# power_supply_bot.net
KiCad netlist of a schematic drawn in EAGLE
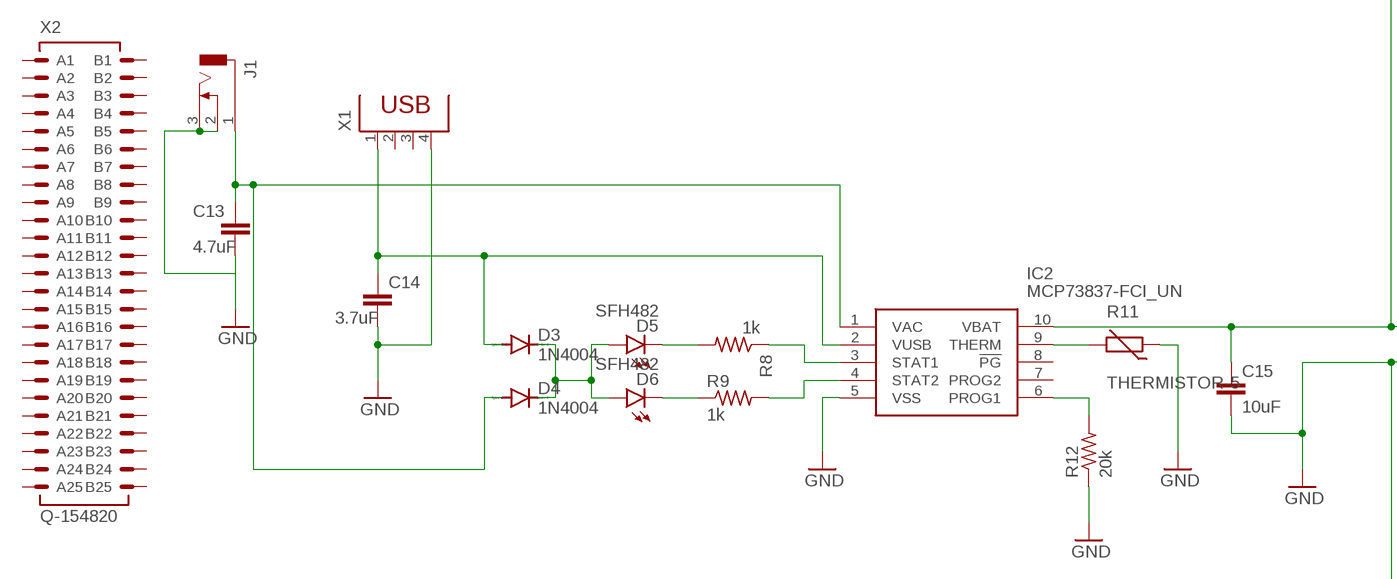
[diagram p0: schematic, sheet 1, part 1 of 2]
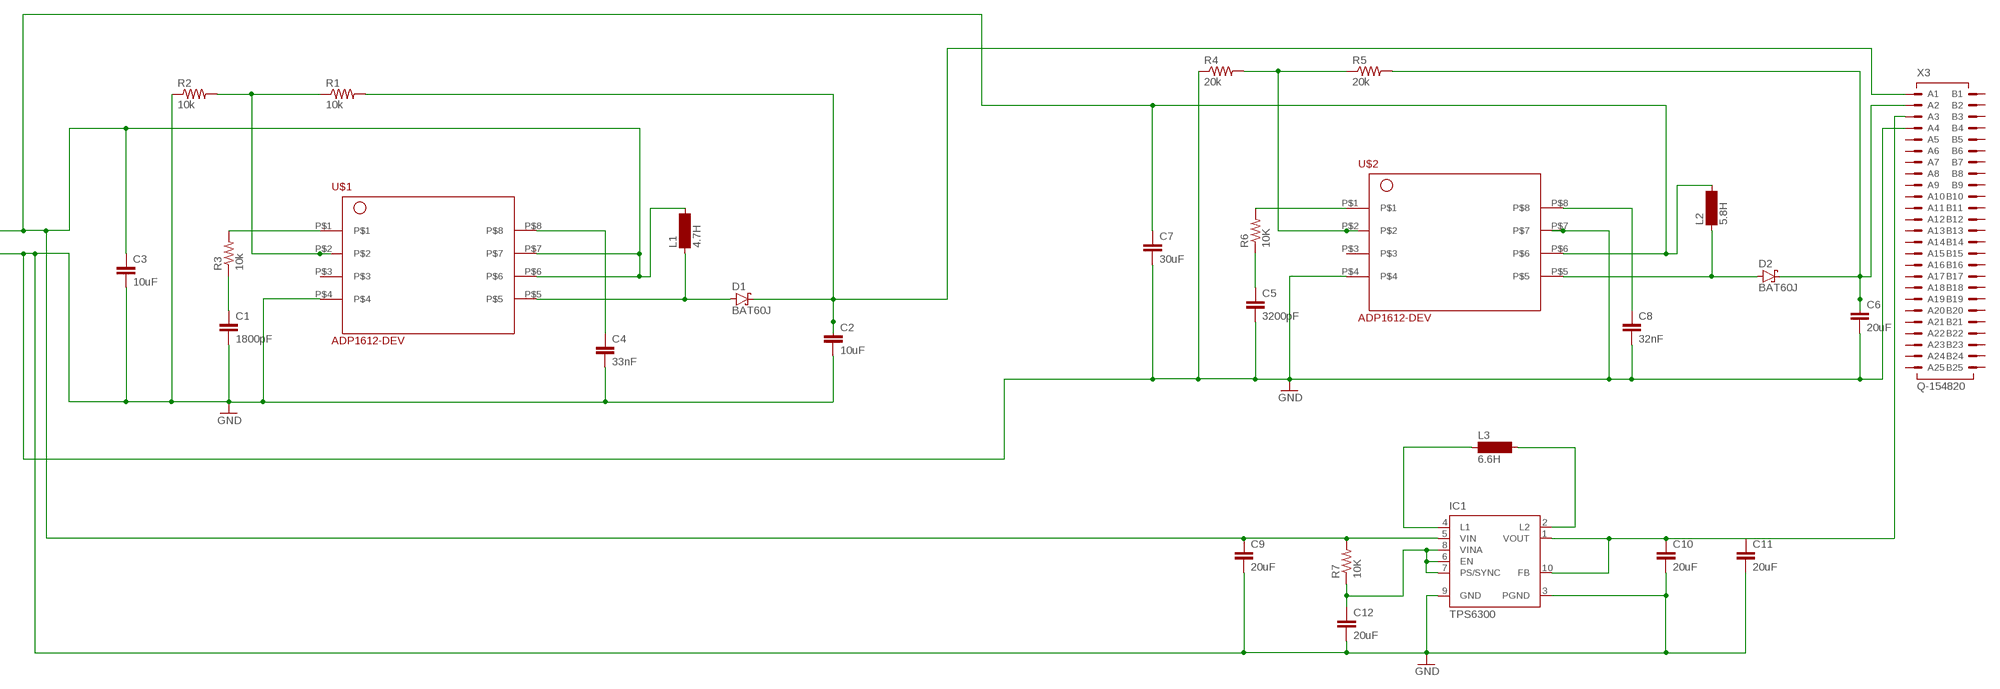
[diagram p1: schematic, sheet 1, part 2 of 2]

(export (version "E")
  (design (tool "Eeschema 10.0.6"))
  (components
    (comp (ref "C1")
      (value "1800pF")
      (footprint "eagle-import:C2.5-4")
      (libsource (lib "eagle-import") (part "C2.5/4"))
    )
    (comp (ref "C2")
      (value "10uF")
      (footprint "eagle-import:C2.5-4")
      (libsource (lib "eagle-import") (part "C2.5/4"))
    )
    (comp (ref "C3")
      (value "10uF")
      (footprint "eagle-import:C2.5-4")
      (libsource (lib "eagle-import") (part "C2.5/4"))
    )
    (comp (ref "C4")
      (value "33nF")
      (footprint "eagle-import:C2.5-4")
      (libsource (lib "eagle-import") (part "C2.5/4"))
    )
    (comp (ref "C5")
      (value "3200pF")
      (footprint "eagle-import:C2.5-4")
      (libsource (lib "eagle-import") (part "C2.5/4"))
    )
    (comp (ref "C6")
      (value "20uF")
      (footprint "eagle-import:C2.5-4")
      (libsource (lib "eagle-import") (part "C2.5/4"))
    )
    (comp (ref "C7")
      (value "30uF")
      (footprint "eagle-import:C2.5-4")
      (libsource (lib "eagle-import") (part "C2.5/4"))
    )
    (comp (ref "C8")
      (value "32nF")
      (footprint "eagle-import:C2.5-4")
      (libsource (lib "eagle-import") (part "C2.5/4"))
    )
    (comp (ref "C9")
      (value "20uF")
      (footprint "eagle-import:C2.5-3")
      (libsource (lib "eagle-import") (part "C2,5-3"))
    )
    (comp (ref "C10")
      (value "20uF")
      (footprint "eagle-import:C2.5-3")
      (libsource (lib "eagle-import") (part "C2,5-3"))
    )
    (comp (ref "C11")
      (value "20uF")
      (footprint "eagle-import:C2.5-3")
      (libsource (lib "eagle-import") (part "C2,5-3"))
    )
    (comp (ref "C12")
      (value "20uF")
      (footprint "eagle-import:C2.5-3")
      (libsource (lib "eagle-import") (part "C2,5-3"))
    )
    (comp (ref "C13")
      (value "4.7uF")
      (footprint "eagle-import:C2.5-3")
      (libsource (lib "eagle-import") (part "C2,5-3"))
    )
    (comp (ref "C14")
      (value "3.7uF")
      (footprint "eagle-import:C2.5-3")
      (libsource (lib "eagle-import") (part "C2,5-3"))
    )
    (comp (ref "C15")
      (value "10uF")
      (footprint "eagle-import:C2.5-3")
      (libsource (lib "eagle-import") (part "C2,5-3"))
    )
    (comp (ref "D1")
      (value "BAT60J")
      (footprint "eagle-import:SOD323_ST")
      (libsource (lib "eagle-import") (part "BAT60J"))
    )
    (comp (ref "D2")
      (value "BAT60J")
      (footprint "eagle-import:SOD323_ST")
      (libsource (lib "eagle-import") (part "BAT60J"))
    )
    (comp (ref "D3")
      (value "1N4004")
      (footprint "eagle-import:DO41-10")
      (libsource (lib "eagle-import") (part "1N4004"))
    )
    (comp (ref "D4")
      (value "1N4004")
      (footprint "eagle-import:DO41-10")
      (libsource (lib "eagle-import") (part "1N4004"))
    )
    (comp (ref "D5")
      (value "SFH482")
      (footprint "eagle-import:SFH482")
      (libsource (lib "eagle-import") (part "SFH482"))
    )
    (comp (ref "D6")
      (value "SFH482")
      (footprint "eagle-import:SFH482")
      (libsource (lib "eagle-import") (part "SFH482"))
    )
    (comp (ref "IC1")
      (value "TPS6300")
      (footprint "eagle-import:DRC-S-PVSON-N10")
      (fields (field (name "MPN") "TPS63000DRCTG4"))
      (libsource (lib "eagle-import") (part "TPS6300"))
    )
    (comp (ref "IC2")
      (value "MCP73837-FCI_UN")
      (footprint "eagle-import:SOP50P490X110-10N")
      (fields
        (field (name "ARROW_PART_NUMBER") "MCP73837-FCI/UN")
        (field (name "MOUSER_PART_NUMBER") "579-MCP73837-FCI/UN")
      )
      (libsource (lib "eagle-import") (part "MCP73837-FCI_UN"))
    )
    (comp (ref "J1")
      (value "DCJ0303")
      (footprint "eagle-import:DCJ0303")
      (libsource (lib "eagle-import") (part "DCJ0303"))
    )
    (comp (ref "L1")
      (value "4.7H")
      (footprint "eagle-import:BS11")
      (libsource (lib "eagle-import") (part "BS11"))
    )
    (comp (ref "L2")
      (value "5.8H")
      (footprint "eagle-import:BS11")
      (libsource (lib "eagle-import") (part "BS11"))
    )
    (comp (ref "L3")
      (value "6.6H")
      (footprint "eagle-import:BS75")
      (libsource (lib "eagle-import") (part "BS75"))
    )
    (comp (ref "R1")
      (value "10k")
      (footprint "eagle-import:0204_7")
      (libsource (lib "eagle-import") (part "R-US_0204/7"))
    )
    (comp (ref "R2")
      (value "10k")
      (footprint "eagle-import:0204_7")
      (libsource (lib "eagle-import") (part "R-US_0204/7"))
    )
    (comp (ref "R3")
      (value "10k")
      (footprint "eagle-import:0204_7")
      (libsource (lib "eagle-import") (part "R-US_0204/7"))
    )
    (comp (ref "R4")
      (value "20k")
      (footprint "eagle-import:0204_7")
      (libsource (lib "eagle-import") (part "R-US_0204/7"))
    )
    (comp (ref "R5")
      (value "20k")
      (footprint "eagle-import:0204_7")
      (libsource (lib "eagle-import") (part "R-US_0204/7"))
    )
    (comp (ref "R6")
      (value "10K")
      (footprint "eagle-import:0204_7")
      (libsource (lib "eagle-import") (part "R-US_0204/7"))
    )
    (comp (ref "R7")
      (value "10K")
      (footprint "eagle-import:0204_5")
      (libsource (lib "eagle-import") (part "R-US_0204/5"))
    )
    (comp (ref "R8")
      (value "1k")
      (footprint "eagle-import:0204_5")
      (libsource (lib "eagle-import") (part "R-US_0204/5"))
    )
    (comp (ref "R9")
      (value "1k")
      (footprint "eagle-import:0204_5")
      (libsource (lib "eagle-import") (part "R-US_0204/5"))
    )
    (comp (ref "R11")
      (value "THERMISTOR-5")
      (footprint "eagle-import:R-5")
      (libsource (lib "eagle-import") (part "THERMISTOR-5"))
    )
    (comp (ref "R12")
      (value "20k")
      (footprint "eagle-import:0204_5")
      (libsource (lib "eagle-import") (part "R-US_0204/5"))
    )
    (comp (ref "U$1")
      (value "ADP1612-DEV")
      (footprint "eagle-import:TQFP-ADP1612")
      (libsource (lib "eagle-import") (part "ADP1612-DEV"))
    )
    (comp (ref "U$2")
      (value "ADP1612-DEV")
      (footprint "eagle-import:TQFP-ADP1612")
      (libsource (lib "eagle-import") (part "ADP1612-DEV"))
    )
    (comp (ref "X1")
      (value "PN61729")
      (footprint "eagle-import:PN61729")
      (libsource (lib "eagle-import") (part "PN61729"))
    )
    (comp (ref "X2")
      (value "Q-154820")
      (footprint "eagle-import:154820")
      (libsource (lib "eagle-import") (part "Q-154820"))
    )
    (comp (ref "X3")
      (value "Q-154820")
      (footprint "eagle-import:154820")
      (libsource (lib "eagle-import") (part "Q-154820"))
    )
  )
  (nets
    (net (code "1") (name "GND") (class "Default")
      (node (ref "C1") (pin "2") (pinfunction "2_2") (pintype "passive"))
      (node (ref "C10") (pin "2") (pinfunction "2_2") (pintype "passive"))
      (node (ref "C11") (pin "2") (pinfunction "2_2") (pintype "passive"))
      (node (ref "C12") (pin "2") (pinfunction "2_2") (pintype "passive"))
      (node (ref "C13") (pin "2") (pinfunction "2_2") (pintype "passive"))
      (node (ref "C14") (pin "1") (pinfunction "1_1") (pintype "passive"))
      (node (ref "C14") (pin "2") (pinfunction "2_2") (pintype "passive"))
      (node (ref "C15") (pin "2") (pinfunction "2_2") (pintype "passive"))
      (node (ref "C2") (pin "2") (pinfunction "2_2") (pintype "passive"))
      (node (ref "C3") (pin "2") (pinfunction "2_2") (pintype "passive"))
      (node (ref "C4") (pin "2") (pinfunction "2_2") (pintype "passive"))
      (node (ref "C5") (pin "2") (pinfunction "2_2") (pintype "passive"))
      (node (ref "C6") (pin "2") (pinfunction "2_2") (pintype "passive"))
      (node (ref "C7") (pin "2") (pinfunction "2_2") (pintype "passive"))
      (node (ref "C8") (pin "2") (pinfunction "2_2") (pintype "passive"))
      (node (ref "C9") (pin "2") (pinfunction "2_2") (pintype "passive"))
      (node (ref "D3") (pin "A") (pinfunction "A_A") (pintype "passive"))
      (node (ref "IC1") (pin "3") (pinfunction "PGND_3") (pintype "power_in"))
      (node (ref "IC1") (pin "9") (pinfunction "GND_9") (pintype "power_in"))
      (node (ref "IC2") (pin "2") (pinfunction "VUSB_2") (pintype "bidirectional"))
      (node (ref "IC2") (pin "5") (pinfunction "VSS_5") (pintype "power_in"))
      (node (ref "J1") (pin "2") (pinfunction "2_2") (pintype "passive"))
      (node (ref "J1") (pin "3") (pinfunction "3_3") (pintype "passive"))
      (node (ref "R11") (pin "1") (pinfunction "1_1") (pintype "passive"))
      (node (ref "R12") (pin "1") (pinfunction "1_1") (pintype "passive"))
      (node (ref "R2") (pin "1") (pinfunction "1_1") (pintype "passive"))
      (node (ref "R4") (pin "1") (pinfunction "1_1") (pintype "passive"))
      (node (ref "U$1") (pin "P$4") (pinfunction "P$4_P$4") (pintype "bidirectional"))
      (node (ref "U$2") (pin "P$4") (pinfunction "P$4_P$4") (pintype "bidirectional"))
      (node (ref "U$2") (pin "P$7") (pinfunction "P$7_P$7") (pintype "bidirectional"))
      (node (ref "X1") (pin "1") (pinfunction "1_1") (pintype "passive"))
      (node (ref "X1") (pin "4") (pinfunction "4_4") (pintype "passive"))
      (node (ref "X3") (pin "A4") (pinfunction "A4_A4") (pintype "passive"))
    )
    (net (code "2") (name "Net-(C1-Pad1)") (class "Default")
      (node (ref "C1") (pin "1") (pinfunction "1_1") (pintype "passive"))
      (node (ref "R3") (pin "1") (pinfunction "1_1") (pintype "passive"))
    )
    (net (code "3") (name "Net-(C2-Pad1)") (class "Default")
      (node (ref "C2") (pin "1") (pinfunction "1_1") (pintype "passive"))
      (node (ref "D1") (pin "C") (pinfunction "C_C") (pintype "passive"))
      (node (ref "R1") (pin "2") (pinfunction "2_2") (pintype "passive"))
      (node (ref "X3") (pin "A1") (pinfunction "A1_A1") (pintype "passive"))
    )
    (net (code "4") (name "Net-(C4-Pad1)") (class "Default")
      (node (ref "C4") (pin "1") (pinfunction "1_1") (pintype "passive"))
      (node (ref "U$1") (pin "P$8") (pinfunction "P$8_P$8") (pintype "bidirectional"))
    )
    (net (code "5") (name "Net-(C5-Pad1)") (class "Default")
      (node (ref "C5") (pin "1") (pinfunction "1_1") (pintype "passive"))
      (node (ref "R6") (pin "1") (pinfunction "1_1") (pintype "passive"))
    )
    (net (code "6") (name "Net-(C6-Pad1)") (class "Default")
      (node (ref "C6") (pin "1") (pinfunction "1_1") (pintype "passive"))
      (node (ref "D2") (pin "C") (pinfunction "C_C") (pintype "passive"))
      (node (ref "R5") (pin "2") (pinfunction "2_2") (pintype "passive"))
      (node (ref "X3") (pin "A2") (pinfunction "A2_A2") (pintype "passive"))
    )
    (net (code "7") (name "Net-(C8-Pad1)") (class "Default")
      (node (ref "C8") (pin "1") (pinfunction "1_1") (pintype "passive"))
      (node (ref "U$2") (pin "P$8") (pinfunction "P$8_P$8") (pintype "bidirectional"))
    )
    (net (code "8") (name "Net-(D1-PadA)") (class "Default")
      (node (ref "D1") (pin "A") (pinfunction "A_A") (pintype "passive"))
      (node (ref "L1") (pin "1") (pinfunction "1_1") (pintype "passive"))
      (node (ref "U$1") (pin "P$5") (pinfunction "P$5_P$5") (pintype "bidirectional"))
    )
    (net (code "9") (name "Net-(D2-PadA)") (class "Default")
      (node (ref "D2") (pin "A") (pinfunction "A_A") (pintype "passive"))
      (node (ref "L2") (pin "1") (pinfunction "1_1") (pintype "passive"))
      (node (ref "U$2") (pin "P$5") (pinfunction "P$5_P$5") (pintype "bidirectional"))
    )
    (net (code "10") (name "Net-(D3-PadC)") (class "Default")
      (node (ref "D3") (pin "C") (pinfunction "C_C") (pintype "passive"))
      (node (ref "D4") (pin "C") (pinfunction "C_C") (pintype "passive"))
      (node (ref "D5") (pin "A") (pinfunction "A_A") (pintype "passive"))
      (node (ref "D6") (pin "A") (pinfunction "A_A") (pintype "passive"))
    )
    (net (code "11") (name "Net-(D5-C)") (class "Default")
      (node (ref "D5") (pin "K") (pinfunction "C_K") (pintype "passive"))
      (node (ref "R8") (pin "2") (pinfunction "2_2") (pintype "passive"))
    )
    (net (code "12") (name "Net-(D6-C)") (class "Default")
      (node (ref "D6") (pin "K") (pinfunction "C_K") (pintype "passive"))
      (node (ref "R9") (pin "1") (pinfunction "1_1") (pintype "passive"))
    )
    (net (code "13") (name "Net-(IC1A-EN)") (class "Default")
      (node (ref "C12") (pin "1") (pinfunction "1_1") (pintype "passive"))
      (node (ref "IC1") (pin "6") (pinfunction "EN_6") (pintype "input"))
      (node (ref "IC1") (pin "7") (pinfunction "PS/SYNC_7") (pintype "input"))
      (node (ref "IC1") (pin "8") (pinfunction "VINA_8") (pintype "input"))
      (node (ref "R7") (pin "1") (pinfunction "1_1") (pintype "passive"))
    )
    (net (code "14") (name "Net-(IC1A-FB)") (class "Default")
      (node (ref "C10") (pin "1") (pinfunction "1_1") (pintype "passive"))
      (node (ref "C11") (pin "1") (pinfunction "1_1") (pintype "passive"))
      (node (ref "IC1") (pin "1") (pinfunction "VOUT_1") (pintype "output"))
      (node (ref "IC1") (pin "10") (pinfunction "FB_10") (pintype "input"))
      (node (ref "X3") (pin "A3") (pinfunction "A3_A3") (pintype "passive"))
    )
    (net (code "15") (name "Net-(IC1A-L1)") (class "Default")
      (node (ref "IC1") (pin "4") (pinfunction "L1_4") (pintype "passive"))
      (node (ref "L3") (pin "1") (pinfunction "1_1") (pintype "passive"))
    )
    (net (code "16") (name "Net-(IC1A-L2)") (class "Default")
      (node (ref "IC1") (pin "2") (pinfunction "L2_2") (pintype "passive"))
      (node (ref "L3") (pin "2") (pinfunction "2_2") (pintype "passive"))
    )
    (net (code "17") (name "Net-(IC1A-VIN)") (class "Default")
      (node (ref "C15") (pin "1") (pinfunction "1_1") (pintype "passive"))
      (node (ref "C3") (pin "1") (pinfunction "1_1") (pintype "passive"))
      (node (ref "C7") (pin "1") (pinfunction "1_1") (pintype "passive"))
      (node (ref "C9") (pin "1") (pinfunction "1_1") (pintype "passive"))
      (node (ref "IC1") (pin "5") (pinfunction "VIN_5") (pintype "input"))
      (node (ref "IC2") (pin "10") (pinfunction "VBAT_10") (pintype "bidirectional"))
      (node (ref "L1") (pin "2") (pinfunction "2_2") (pintype "passive"))
      (node (ref "L2") (pin "2") (pinfunction "2_2") (pintype "passive"))
      (node (ref "R7") (pin "2") (pinfunction "2_2") (pintype "passive"))
      (node (ref "U$1") (pin "P$6") (pinfunction "P$6_P$6") (pintype "bidirectional"))
      (node (ref "U$1") (pin "P$7") (pinfunction "P$7_P$7") (pintype "bidirectional"))
      (node (ref "U$2") (pin "P$6") (pinfunction "P$6_P$6") (pintype "bidirectional"))
    )
    (net (code "18") (name "Net-(IC2-PROG1)") (class "Default")
      (node (ref "IC2") (pin "6") (pinfunction "PROG1_6") (pintype "bidirectional"))
      (node (ref "R12") (pin "2") (pinfunction "2_2") (pintype "passive"))
    )
    (net (code "19") (name "Net-(IC2-STAT1)") (class "Default")
      (node (ref "IC2") (pin "3") (pinfunction "STAT1_3") (pintype "bidirectional"))
      (node (ref "R8") (pin "1") (pinfunction "1_1") (pintype "passive"))
    )
    (net (code "20") (name "Net-(IC2-STAT2)") (class "Default")
      (node (ref "IC2") (pin "4") (pinfunction "STAT2_4") (pintype "bidirectional"))
      (node (ref "R9") (pin "2") (pinfunction "2_2") (pintype "passive"))
    )
    (net (code "21") (name "Net-(IC2-THERM)") (class "Default")
      (node (ref "IC2") (pin "9") (pinfunction "THERM_9") (pintype "bidirectional"))
      (node (ref "R11") (pin "2") (pinfunction "2_2") (pintype "passive"))
    )
    (net (code "22") (name "Net-(IC2-VAC)") (class "Default")
      (node (ref "C13") (pin "1") (pinfunction "1_1") (pintype "passive"))
      (node (ref "D4") (pin "A") (pinfunction "A_A") (pintype "passive"))
      (node (ref "IC2") (pin "1") (pinfunction "VAC_1") (pintype "bidirectional"))
      (node (ref "J1") (pin "1") (pinfunction "1_1") (pintype "passive"))
    )
    (net (code "23") (name "Net-(R1-Pad1)") (class "Default")
      (node (ref "R1") (pin "1") (pinfunction "1_1") (pintype "passive"))
      (node (ref "R2") (pin "2") (pinfunction "2_2") (pintype "passive"))
      (node (ref "U$1") (pin "P$2") (pinfunction "P$2_P$2") (pintype "bidirectional"))
    )
    (net (code "24") (name "Net-(R3-Pad2)") (class "Default")
      (node (ref "R3") (pin "2") (pinfunction "2_2") (pintype "passive"))
      (node (ref "U$1") (pin "P$1") (pinfunction "P$1_P$1") (pintype "bidirectional"))
    )
    (net (code "25") (name "Net-(R4-Pad2)") (class "Default")
      (node (ref "R4") (pin "2") (pinfunction "2_2") (pintype "passive"))
      (node (ref "R5") (pin "1") (pinfunction "1_1") (pintype "passive"))
      (node (ref "U$2") (pin "P$2") (pinfunction "P$2_P$2") (pintype "bidirectional"))
    )
    (net (code "26") (name "Net-(R6-Pad2)") (class "Default")
      (node (ref "R6") (pin "2") (pinfunction "2_2") (pintype "passive"))
      (node (ref "U$2") (pin "P$1") (pinfunction "P$1_P$1") (pintype "bidirectional"))
    )
    (net (code "27") (name "unconnected-(IC2-PROG2-Pad7)") (class "Default")
      (node (ref "IC2") (pin "7") (pinfunction "PROG2_7") (pintype "bidirectional"))
    )
    (net (code "28") (name "unconnected-(IC2-~{PG}-Pad8)") (class "Default")
      (node (ref "IC2") (pin "8") (pinfunction "~{PG}_8") (pintype "bidirectional"))
    )
    (net (code "29") (name "unconnected-(U$1-PadP$3)") (class "Default")
      (node (ref "U$1") (pin "P$3") (pinfunction "P$3_P$3") (pintype "bidirectional"))
    )
    (net (code "30") (name "unconnected-(U$2-PadP$3)") (class "Default")
      (node (ref "U$2") (pin "P$3") (pinfunction "P$3_P$3") (pintype "bidirectional"))
    )
    (net (code "31") (name "unconnected-(X1-Pad2)") (class "Default")
      (node (ref "X1") (pin "2") (pinfunction "2_2") (pintype "passive"))
    )
    (net (code "32") (name "unconnected-(X1-Pad3)") (class "Default")
      (node (ref "X1") (pin "3") (pinfunction "3_3") (pintype "passive"))
    )
    (net (code "33") (name "unconnected-(X2-PadA1)") (class "Default")
      (node (ref "X2") (pin "A1") (pinfunction "A1_A1") (pintype "passive"))
    )
    (net (code "34") (name "unconnected-(X2-PadA2)") (class "Default")
      (node (ref "X2") (pin "A2") (pinfunction "A2_A2") (pintype "passive"))
    )
    (net (code "35") (name "unconnected-(X2-PadA3)") (class "Default")
      (node (ref "X2") (pin "A3") (pinfunction "A3_A3") (pintype "passive"))
    )
    (net (code "36") (name "unconnected-(X2-PadA4)") (class "Default")
      (node (ref "X2") (pin "A4") (pinfunction "A4_A4") (pintype "passive"))
    )
    (net (code "37") (name "unconnected-(X2-PadA5)") (class "Default")
      (node (ref "X2") (pin "A5") (pinfunction "A5_A5") (pintype "passive"))
    )
    (net (code "38") (name "unconnected-(X2-PadA6)") (class "Default")
      (node (ref "X2") (pin "A6") (pinfunction "A6_A6") (pintype "passive"))
    )
    (net (code "39") (name "unconnected-(X2-PadA7)") (class "Default")
      (node (ref "X2") (pin "A7") (pinfunction "A7_A7") (pintype "passive"))
    )
    (net (code "40") (name "unconnected-(X2-PadA8)") (class "Default")
      (node (ref "X2") (pin "A8") (pinfunction "A8_A8") (pintype "passive"))
    )
    (net (code "41") (name "unconnected-(X2-PadA9)") (class "Default")
      (node (ref "X2") (pin "A9") (pinfunction "A9_A9") (pintype "passive"))
    )
    (net (code "42") (name "unconnected-(X2-PadA10)") (class "Default")
      (node (ref "X2") (pin "A10") (pinfunction "A10_A10") (pintype "passive"))
    )
    (net (code "43") (name "unconnected-(X2-PadA11)") (class "Default")
      (node (ref "X2") (pin "A11") (pinfunction "A11_A11") (pintype "passive"))
    )
    (net (code "44") (name "unconnected-(X2-PadA12)") (class "Default")
      (node (ref "X2") (pin "A12") (pinfunction "A12_A12") (pintype "passive"))
    )
    (net (code "45") (name "unconnected-(X2-PadA13)") (class "Default")
      (node (ref "X2") (pin "A13") (pinfunction "A13_A13") (pintype "passive"))
    )
    (net (code "46") (name "unconnected-(X2-PadA14)") (class "Default")
      (node (ref "X2") (pin "A14") (pinfunction "A14_A14") (pintype "passive"))
    )
    (net (code "47") (name "unconnected-(X2-PadA15)") (class "Default")
      (node (ref "X2") (pin "A15") (pinfunction "A15_A15") (pintype "passive"))
    )
    (net (code "48") (name "unconnected-(X2-PadA16)") (class "Default")
      (node (ref "X2") (pin "A16") (pinfunction "A16_A16") (pintype "passive"))
    )
    (net (code "49") (name "unconnected-(X2-PadA17)") (class "Default")
      (node (ref "X2") (pin "A17") (pinfunction "A17_A17") (pintype "passive"))
    )
    (net (code "50") (name "unconnected-(X2-PadA18)") (class "Default")
      (node (ref "X2") (pin "A18") (pinfunction "A18_A18") (pintype "passive"))
    )
    (net (code "51") (name "unconnected-(X2-PadA19)") (class "Default")
      (node (ref "X2") (pin "A19") (pinfunction "A19_A19") (pintype "passive"))
    )
    (net (code "52") (name "unconnected-(X2-PadA20)") (class "Default")
      (node (ref "X2") (pin "A20") (pinfunction "A20_A20") (pintype "passive"))
    )
    (net (code "53") (name "unconnected-(X2-PadA21)") (class "Default")
      (node (ref "X2") (pin "A21") (pinfunction "A21_A21") (pintype "passive"))
    )
    (net (code "54") (name "unconnected-(X2-PadA22)") (class "Default")
      (node (ref "X2") (pin "A22") (pinfunction "A22_A22") (pintype "passive"))
    )
    (net (code "55") (name "unconnected-(X2-PadA23)") (class "Default")
      (node (ref "X2") (pin "A23") (pinfunction "A23_A23") (pintype "passive"))
    )
    (net (code "56") (name "unconnected-(X2-PadA24)") (class "Default")
      (node (ref "X2") (pin "A24") (pinfunction "A24_A24") (pintype "passive"))
    )
    (net (code "57") (name "unconnected-(X2-PadA25)") (class "Default")
      (node (ref "X2") (pin "A25") (pinfunction "A25_A25") (pintype "passive"))
    )
    (net (code "58") (name "unconnected-(X2-PadB1)") (class "Default")
      (node (ref "X2") (pin "B1") (pinfunction "B1_B1") (pintype "passive"))
    )
    (net (code "59") (name "unconnected-(X2-PadB2)") (class "Default")
      (node (ref "X2") (pin "B2") (pinfunction "B2_B2") (pintype "passive"))
    )
    (net (code "60") (name "unconnected-(X2-PadB3)") (class "Default")
      (node (ref "X2") (pin "B3") (pinfunction "B3_B3") (pintype "passive"))
    )
    (net (code "61") (name "unconnected-(X2-PadB4)") (class "Default")
      (node (ref "X2") (pin "B4") (pinfunction "B4_B4") (pintype "passive"))
    )
    (net (code "62") (name "unconnected-(X2-PadB5)") (class "Default")
      (node (ref "X2") (pin "B5") (pinfunction "B5_B5") (pintype "passive"))
    )
    (net (code "63") (name "unconnected-(X2-PadB6)") (class "Default")
      (node (ref "X2") (pin "B6") (pinfunction "B6_B6") (pintype "passive"))
    )
    (net (code "64") (name "unconnected-(X2-PadB7)") (class "Default")
      (node (ref "X2") (pin "B7") (pinfunction "B7_B7") (pintype "passive"))
    )
    (net (code "65") (name "unconnected-(X2-PadB8)") (class "Default")
      (node (ref "X2") (pin "B8") (pinfunction "B8_B8") (pintype "passive"))
    )
    (net (code "66") (name "unconnected-(X2-PadB9)") (class "Default")
      (node (ref "X2") (pin "B9") (pinfunction "B9_B9") (pintype "passive"))
    )
    (net (code "67") (name "unconnected-(X2-PadB10)") (class "Default")
      (node (ref "X2") (pin "B10") (pinfunction "B10_B10") (pintype "passive"))
    )
    (net (code "68") (name "unconnected-(X2-PadB11)") (class "Default")
      (node (ref "X2") (pin "B11") (pinfunction "B11_B11") (pintype "passive"))
    )
    (net (code "69") (name "unconnected-(X2-PadB12)") (class "Default")
      (node (ref "X2") (pin "B12") (pinfunction "B12_B12") (pintype "passive"))
    )
    (net (code "70") (name "unconnected-(X2-PadB13)") (class "Default")
      (node (ref "X2") (pin "B13") (pinfunction "B13_B13") (pintype "passive"))
    )
    (net (code "71") (name "unconnected-(X2-PadB14)") (class "Default")
      (node (ref "X2") (pin "B14") (pinfunction "B14_B14") (pintype "passive"))
    )
    (net (code "72") (name "unconnected-(X2-PadB15)") (class "Default")
      (node (ref "X2") (pin "B15") (pinfunction "B15_B15") (pintype "passive"))
    )
    (net (code "73") (name "unconnected-(X2-PadB16)") (class "Default")
      (node (ref "X2") (pin "B16") (pinfunction "B16_B16") (pintype "passive"))
    )
    (net (code "74") (name "unconnected-(X2-PadB17)") (class "Default")
      (node (ref "X2") (pin "B17") (pinfunction "B17_B17") (pintype "passive"))
    )
    (net (code "75") (name "unconnected-(X2-PadB18)") (class "Default")
      (node (ref "X2") (pin "B18") (pinfunction "B18_B18") (pintype "passive"))
    )
    (net (code "76") (name "unconnected-(X2-PadB19)") (class "Default")
      (node (ref "X2") (pin "B19") (pinfunction "B19_B19") (pintype "passive"))
    )
    (net (code "77") (name "unconnected-(X2-PadB20)") (class "Default")
      (node (ref "X2") (pin "B20") (pinfunction "B20_B20") (pintype "passive"))
    )
    (net (code "78") (name "unconnected-(X2-PadB21)") (class "Default")
      (node (ref "X2") (pin "B21") (pinfunction "B21_B21") (pintype "passive"))
    )
    (net (code "79") (name "unconnected-(X2-PadB22)") (class "Default")
      (node (ref "X2") (pin "B22") (pinfunction "B22_B22") (pintype "passive"))
    )
    (net (code "80") (name "unconnected-(X2-PadB23)") (class "Default")
      (node (ref "X2") (pin "B23") (pinfunction "B23_B23") (pintype "passive"))
    )
    (net (code "81") (name "unconnected-(X2-PadB24)") (class "Default")
      (node (ref "X2") (pin "B24") (pinfunction "B24_B24") (pintype "passive"))
    )
    (net (code "82") (name "unconnected-(X2-PadB25)") (class "Default")
      (node (ref "X2") (pin "B25") (pinfunction "B25_B25") (pintype "passive"))
    )
    (net (code "83") (name "unconnected-(X3-PadA5)") (class "Default")
      (node (ref "X3") (pin "A5") (pinfunction "A5_A5") (pintype "passive"))
    )
    (net (code "84") (name "unconnected-(X3-PadA6)") (class "Default")
      (node (ref "X3") (pin "A6") (pinfunction "A6_A6") (pintype "passive"))
    )
    (net (code "85") (name "unconnected-(X3-PadA7)") (class "Default")
      (node (ref "X3") (pin "A7") (pinfunction "A7_A7") (pintype "passive"))
    )
    (net (code "86") (name "unconnected-(X3-PadA8)") (class "Default")
      (node (ref "X3") (pin "A8") (pinfunction "A8_A8") (pintype "passive"))
    )
    (net (code "87") (name "unconnected-(X3-PadA9)") (class "Default")
      (node (ref "X3") (pin "A9") (pinfunction "A9_A9") (pintype "passive"))
    )
    (net (code "88") (name "unconnected-(X3-PadA10)") (class "Default")
      (node (ref "X3") (pin "A10") (pinfunction "A10_A10") (pintype "passive"))
    )
    (net (code "89") (name "unconnected-(X3-PadA11)") (class "Default")
      (node (ref "X3") (pin "A11") (pinfunction "A11_A11") (pintype "passive"))
    )
    (net (code "90") (name "unconnected-(X3-PadA12)") (class "Default")
      (node (ref "X3") (pin "A12") (pinfunction "A12_A12") (pintype "passive"))
    )
    (net (code "91") (name "unconnected-(X3-PadA13)") (class "Default")
      (node (ref "X3") (pin "A13") (pinfunction "A13_A13") (pintype "passive"))
    )
    (net (code "92") (name "unconnected-(X3-PadA14)") (class "Default")
      (node (ref "X3") (pin "A14") (pinfunction "A14_A14") (pintype "passive"))
    )
    (net (code "93") (name "unconnected-(X3-PadA15)") (class "Default")
      (node (ref "X3") (pin "A15") (pinfunction "A15_A15") (pintype "passive"))
    )
    (net (code "94") (name "unconnected-(X3-PadA16)") (class "Default")
      (node (ref "X3") (pin "A16") (pinfunction "A16_A16") (pintype "passive"))
    )
    (net (code "95") (name "unconnected-(X3-PadA17)") (class "Default")
      (node (ref "X3") (pin "A17") (pinfunction "A17_A17") (pintype "passive"))
    )
    (net (code "96") (name "unconnected-(X3-PadA18)") (class "Default")
      (node (ref "X3") (pin "A18") (pinfunction "A18_A18") (pintype "passive"))
    )
    (net (code "97") (name "unconnected-(X3-PadA19)") (class "Default")
      (node (ref "X3") (pin "A19") (pinfunction "A19_A19") (pintype "passive"))
    )
    (net (code "98") (name "unconnected-(X3-PadA20)") (class "Default")
      (node (ref "X3") (pin "A20") (pinfunction "A20_A20") (pintype "passive"))
    )
    (net (code "99") (name "unconnected-(X3-PadA21)") (class "Default")
      (node (ref "X3") (pin "A21") (pinfunction "A21_A21") (pintype "passive"))
    )
    (net (code "100") (name "unconnected-(X3-PadA22)") (class "Default")
      (node (ref "X3") (pin "A22") (pinfunction "A22_A22") (pintype "passive"))
    )
    (net (code "101") (name "unconnected-(X3-PadA23)") (class "Default")
      (node (ref "X3") (pin "A23") (pinfunction "A23_A23") (pintype "passive"))
    )
    (net (code "102") (name "unconnected-(X3-PadA24)") (class "Default")
      (node (ref "X3") (pin "A24") (pinfunction "A24_A24") (pintype "passive"))
    )
    (net (code "103") (name "unconnected-(X3-PadA25)") (class "Default")
      (node (ref "X3") (pin "A25") (pinfunction "A25_A25") (pintype "passive"))
    )
    (net (code "104") (name "unconnected-(X3-PadB1)") (class "Default")
      (node (ref "X3") (pin "B1") (pinfunction "B1_B1") (pintype "passive"))
    )
    (net (code "105") (name "unconnected-(X3-PadB2)") (class "Default")
      (node (ref "X3") (pin "B2") (pinfunction "B2_B2") (pintype "passive"))
    )
    (net (code "106") (name "unconnected-(X3-PadB3)") (class "Default")
      (node (ref "X3") (pin "B3") (pinfunction "B3_B3") (pintype "passive"))
    )
    (net (code "107") (name "unconnected-(X3-PadB4)") (class "Default")
      (node (ref "X3") (pin "B4") (pinfunction "B4_B4") (pintype "passive"))
    )
    (net (code "108") (name "unconnected-(X3-PadB5)") (class "Default")
      (node (ref "X3") (pin "B5") (pinfunction "B5_B5") (pintype "passive"))
    )
    (net (code "109") (name "unconnected-(X3-PadB6)") (class "Default")
      (node (ref "X3") (pin "B6") (pinfunction "B6_B6") (pintype "passive"))
    )
    (net (code "110") (name "unconnected-(X3-PadB7)") (class "Default")
      (node (ref "X3") (pin "B7") (pinfunction "B7_B7") (pintype "passive"))
    )
    (net (code "111") (name "unconnected-(X3-PadB8)") (class "Default")
      (node (ref "X3") (pin "B8") (pinfunction "B8_B8") (pintype "passive"))
    )
    (net (code "112") (name "unconnected-(X3-PadB9)") (class "Default")
      (node (ref "X3") (pin "B9") (pinfunction "B9_B9") (pintype "passive"))
    )
    (net (code "113") (name "unconnected-(X3-PadB10)") (class "Default")
      (node (ref "X3") (pin "B10") (pinfunction "B10_B10") (pintype "passive"))
    )
    (net (code "114") (name "unconnected-(X3-PadB11)") (class "Default")
      (node (ref "X3") (pin "B11") (pinfunction "B11_B11") (pintype "passive"))
    )
    (net (code "115") (name "unconnected-(X3-PadB12)") (class "Default")
      (node (ref "X3") (pin "B12") (pinfunction "B12_B12") (pintype "passive"))
    )
    (net (code "116") (name "unconnected-(X3-PadB13)") (class "Default")
      (node (ref "X3") (pin "B13") (pinfunction "B13_B13") (pintype "passive"))
    )
    (net (code "117") (name "unconnected-(X3-PadB14)") (class "Default")
      (node (ref "X3") (pin "B14") (pinfunction "B14_B14") (pintype "passive"))
    )
    (net (code "118") (name "unconnected-(X3-PadB15)") (class "Default")
      (node (ref "X3") (pin "B15") (pinfunction "B15_B15") (pintype "passive"))
    )
    (net (code "119") (name "unconnected-(X3-PadB16)") (class "Default")
      (node (ref "X3") (pin "B16") (pinfunction "B16_B16") (pintype "passive"))
    )
    (net (code "120") (name "unconnected-(X3-PadB17)") (class "Default")
      (node (ref "X3") (pin "B17") (pinfunction "B17_B17") (pintype "passive"))
    )
    (net (code "121") (name "unconnected-(X3-PadB18)") (class "Default")
      (node (ref "X3") (pin "B18") (pinfunction "B18_B18") (pintype "passive"))
    )
    (net (code "122") (name "unconnected-(X3-PadB19)") (class "Default")
      (node (ref "X3") (pin "B19") (pinfunction "B19_B19") (pintype "passive"))
    )
    (net (code "123") (name "unconnected-(X3-PadB20)") (class "Default")
      (node (ref "X3") (pin "B20") (pinfunction "B20_B20") (pintype "passive"))
    )
    (net (code "124") (name "unconnected-(X3-PadB21)") (class "Default")
      (node (ref "X3") (pin "B21") (pinfunction "B21_B21") (pintype "passive"))
    )
    (net (code "125") (name "unconnected-(X3-PadB22)") (class "Default")
      (node (ref "X3") (pin "B22") (pinfunction "B22_B22") (pintype "passive"))
    )
    (net (code "126") (name "unconnected-(X3-PadB23)") (class "Default")
      (node (ref "X3") (pin "B23") (pinfunction "B23_B23") (pintype "passive"))
    )
    (net (code "127") (name "unconnected-(X3-PadB24)") (class "Default")
      (node (ref "X3") (pin "B24") (pinfunction "B24_B24") (pintype "passive"))
    )
    (net (code "128") (name "unconnected-(X3-PadB25)") (class "Default")
      (node (ref "X3") (pin "B25") (pinfunction "B25_B25") (pintype "passive"))
    )
  )
)
